# GateDriver.net
KiCad netlist of a schematic drawn in Altium Designer
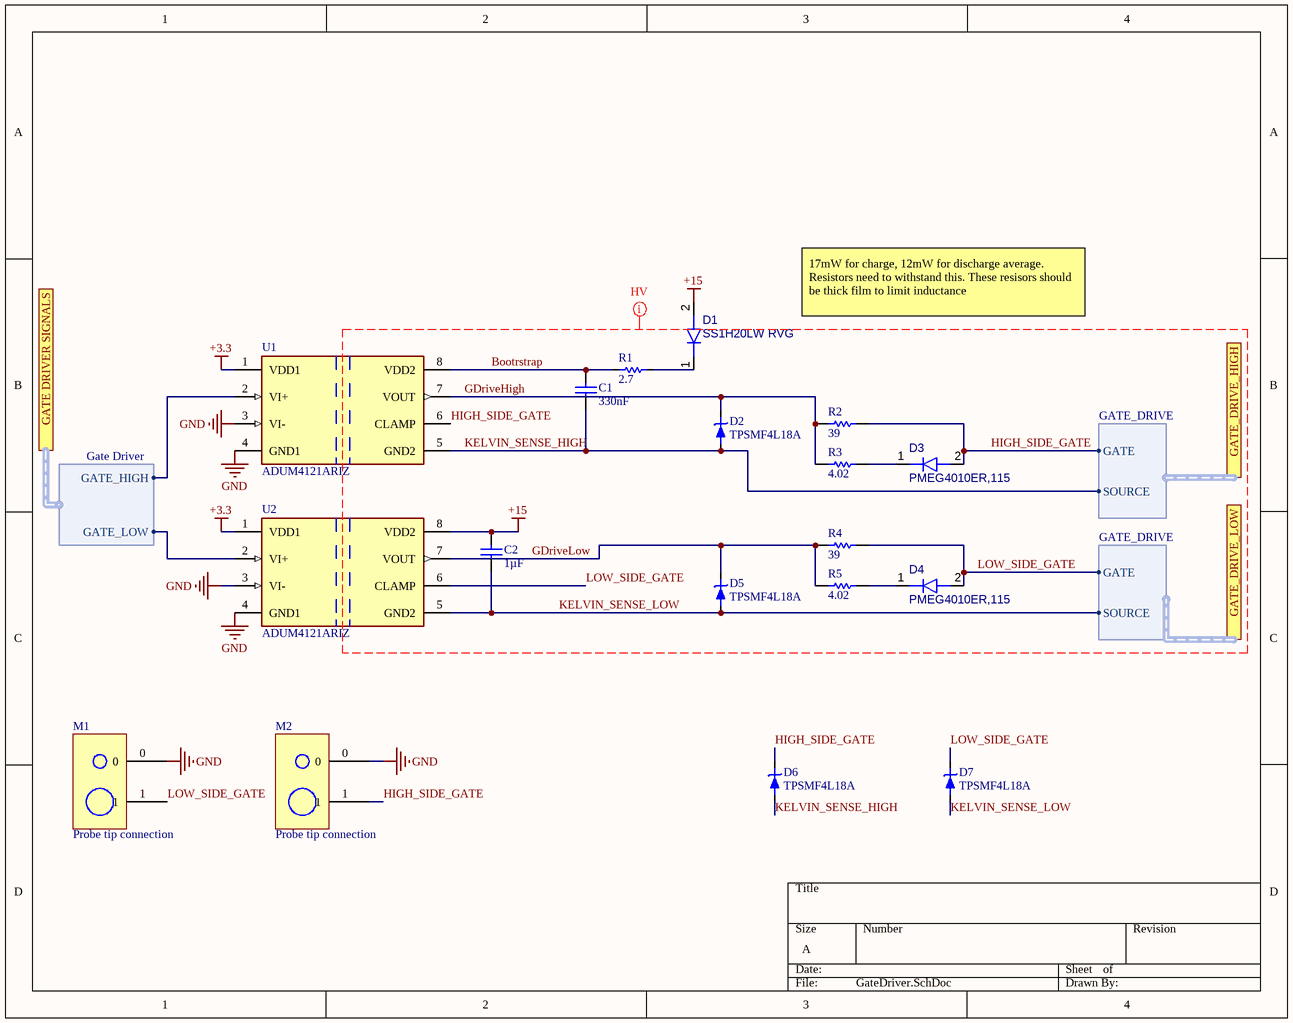
[diagram p0: GateDriver.SchDoc]

(export (version "E")
  (design (tool "Eeschema 10.0.6"))
  (components
    (comp (ref "C1")
      (value "330nF")
      (footprint "1206_CAPACITOR")
      (fields (field (name "TOLERANCE") "10%") (field (name "Comment") "C1206X334K5RACAUTO"))
      (libsource (lib "University of Minnesota - Solar Vehicle Project") (part "Cap"))
    )
    (comp (ref "C2")
      (value "1µF")
      (footprint "0805_Capacitor")
      (description "CAP 0805 1uF 50V")
      (fields (field (name "TOLERANCE") "10%"))
      (libsource (lib "University of Minnesota - Solar Vehicle Project") (part "Cap"))
    )
    (comp (ref "D1")
      (value "SS1H20LW RVG")
      (footprint "PMEG4010ER,115-Footprint-1")
      (description "Rectifier Diode Schottky 200V 1A 2-Pin SOD-123W T/R")
      (libsource (lib "University of Minnesota - Solar Vehicle Project") (part "DIODE-2"))
    )
    (comp (ref "D2")
      (value "TPSMF4L18A")
      (footprint "TPSMF4L18A-Footprint-1")
      (description "TVS DIODE 18V 29.2V SOD123FL")
      (libsource (lib "University of Minnesota - Solar Vehicle Project") (part "D_TV_410V"))
    )
    (comp (ref "D3")
      (value "PMEG4010ER,115")
      (footprint "PMEG4010ER,115-Footprint-1")
      (description "Rectifier Diode, Schottky, 1 Phase, 1 Element, 1A, 40V V(RRM), Silicon")
      (libsource (lib "University of Minnesota - Solar Vehicle Project") (part "DIODE-2"))
    )
    (comp (ref "D4")
      (value "PMEG4010ER,115")
      (footprint "PMEG4010ER,115-Footprint-1")
      (description "Rectifier Diode, Schottky, 1 Phase, 1 Element, 1A, 40V V(RRM), Silicon")
      (libsource (lib "University of Minnesota - Solar Vehicle Project") (part "DIODE-2"))
    )
    (comp (ref "D5")
      (value "TPSMF4L18A")
      (footprint "TPSMF4L18A-Footprint-1")
      (description "TVS DIODE 18V 29.2V SOD123FL")
      (libsource (lib "University of Minnesota - Solar Vehicle Project") (part "D_TV_410V"))
    )
    (comp (ref "D6")
      (value "TPSMF4L18A")
      (footprint "TPSMF4L18A-Footprint-1")
      (description "TVS DIODE 18V 29.2V SOD123FL")
      (libsource (lib "University of Minnesota - Solar Vehicle Project") (part "D_TV_410V"))
    )
    (comp (ref "D7")
      (value "TPSMF4L18A")
      (footprint "TPSMF4L18A-Footprint-1")
      (description "TVS DIODE 18V 29.2V SOD123FL")
      (libsource (lib "University of Minnesota - Solar Vehicle Project") (part "D_TV_410V"))
    )
    (comp (ref "M1")
      (value "Probe tip connection")
      (footprint "Probe tip connection-Footprint-1")
      (description "Connection for oscilscope ground tip")
      (libsource (lib "University of Minnesota - Solar Vehicle Project") (part "Probe tip connection-Symbol-1"))
    )
    (comp (ref "M2")
      (value "Probe tip connection")
      (footprint "Probe tip connection-Footprint-1")
      (description "Connection for oscilscope ground tip")
      (libsource (lib "University of Minnesota - Solar Vehicle Project") (part "Probe tip connection-Symbol-1"))
    )
    (comp (ref "R1")
      (value "2.7")
      (footprint "1210_Resistor")
      (description "RES SMD 2.7 OHM 5% 1/2W 1210")
      (fields (field (name "POWER") "500mW") (field (name "TOLERANCE") "5%"))
      (libsource (lib "University of Minnesota - Solar Vehicle Project") (part "Symbol"))
    )
    (comp (ref "R2")
      (value "39")
      (footprint "0805_Resistor")
      (fields
        (field (name "POWER") "125mW")
        (field (name "TOLERANCE") "5%")
        (field (name "Comment") "RMCF0805JT39R0")
      )
      (libsource (lib "University of Minnesota - Solar Vehicle Project") (part "RES-2"))
    )
    (comp (ref "R3")
      (value "4.02")
      (footprint "0805_Resistor")
      (fields
        (field (name "TOLERANCE") "1%")
        (field (name "POWER") "125mW")
        (field (name "Comment") "CRCW08054R02FKEA")
      )
      (libsource (lib "University of Minnesota - Solar Vehicle Project") (part "RES-2"))
    )
    (comp (ref "R4")
      (value "39")
      (footprint "0805_Resistor")
      (fields
        (field (name "POWER") "125mW")
        (field (name "TOLERANCE") "5%")
        (field (name "Comment") "RMCF0805JT39R0")
      )
      (libsource (lib "University of Minnesota - Solar Vehicle Project") (part "RES-2"))
    )
    (comp (ref "R5")
      (value "4.02")
      (footprint "0805_Resistor")
      (fields
        (field (name "TOLERANCE") "1%")
        (field (name "POWER") "125mW")
        (field (name "Comment") "CRCW08054R02FKEA")
      )
      (libsource (lib "University of Minnesota - Solar Vehicle Project") (part "RES-2"))
    )
    (comp (ref "U1")
      (value "ADUM4121ARIZ")
      (footprint "FP-RI-8-1-IPC_B")
      (description "2A gat driver")
      (libsource (lib "University of Minnesota - Solar Vehicle Project") (part "cd04aab5e6e55e7ffe7a0c5e5a36cba"))
    )
    (comp (ref "U2")
      (value "ADUM4121ARIZ")
      (footprint "FP-RI-8-1-IPC_B")
      (description "2A gat driver")
      (libsource (lib "University of Minnesota - Solar Vehicle Project") (part "cd04aab5e6e55e7ffe7a0c5e5a36cba"))
    )
  )
  (nets
    (net (code "4") (name "+3.3") (class "Default")
      (node (ref "U1") (pin "1") (pinfunction "VDD1_1") (pintype "power_in"))
      (node (ref "U2") (pin "1") (pinfunction "VDD1_1") (pintype "power_in"))
    )
    (net (code "5") (name "+15") (class "Default")
      (node (ref "C2") (pin "2") (pinfunction "2_2") (pintype "passive"))
      (node (ref "D1") (pin "2") (pinfunction "A_2") (pintype "passive"))
      (node (ref "U2") (pin "8") (pinfunction "VDD2_8") (pintype "power_in"))
    )
    (net (code "6") (name "/Bootrstrap") (class "Default")
      (node (ref "C1") (pin "2") (pinfunction "2_2") (pintype "passive"))
      (node (ref "R1") (pin "1") (pinfunction "1_1") (pintype "passive"))
      (node (ref "U1") (pin "8") (pinfunction "VDD2_8") (pintype "power_in"))
    )
    (net (code "7") (name "/GATE_HIGH") (class "Default")
      (node (ref "U1") (pin "2") (pinfunction "VI+_2") (pintype "input"))
    )
    (net (code "8") (name "/GATE_LOW") (class "Default")
      (node (ref "U2") (pin "2") (pinfunction "VI+_2") (pintype "input"))
    )
    (net (code "9") (name "/GDriveHigh") (class "Default")
      (node (ref "D2") (pin "2") (pinfunction "Cathode_2") (pintype "passive"))
      (node (ref "R2") (pin "1") (pinfunction "1_1") (pintype "passive"))
      (node (ref "R3") (pin "1") (pinfunction "1_1") (pintype "passive"))
      (node (ref "U1") (pin "7") (pinfunction "VOUT_7") (pintype "output"))
    )
    (net (code "10") (name "/GDriveLow") (class "Default")
      (node (ref "D5") (pin "2") (pinfunction "Cathode_2") (pintype "passive"))
      (node (ref "R4") (pin "1") (pinfunction "1_1") (pintype "passive"))
      (node (ref "R5") (pin "1") (pinfunction "1_1") (pintype "passive"))
      (node (ref "U2") (pin "7") (pinfunction "VOUT_7") (pintype "output"))
    )
    (net (code "11") (name "/HIGH_SIDE_GATE") (class "Default")
      (node (ref "D3") (pin "2") (pinfunction "A_2") (pintype "passive"))
      (node (ref "D6") (pin "2") (pinfunction "Cathode_2") (pintype "passive"))
      (node (ref "M2") (pin "1") (pinfunction "1_1") (pintype "passive"))
      (node (ref "R2") (pin "2") (pinfunction "2_2") (pintype "passive"))
      (node (ref "U1") (pin "6") (pinfunction "CLAMP_6") (pintype "passive"))
    )
    (net (code "12") (name "/KELVIN_SENSE_HIGH") (class "Default")
      (node (ref "C1") (pin "1") (pinfunction "1_1") (pintype "passive"))
      (node (ref "D2") (pin "1") (pinfunction "Anode_1") (pintype "passive"))
      (node (ref "D6") (pin "1") (pinfunction "Anode_1") (pintype "passive"))
      (node (ref "U1") (pin "5") (pinfunction "GND2_5") (pintype "power_in"))
    )
    (net (code "13") (name "/KELVIN_SENSE_LOW") (class "Default")
      (node (ref "C2") (pin "1") (pinfunction "1_1") (pintype "passive"))
      (node (ref "D5") (pin "1") (pinfunction "Anode_1") (pintype "passive"))
      (node (ref "D7") (pin "1") (pinfunction "Anode_1") (pintype "passive"))
      (node (ref "U2") (pin "5") (pinfunction "GND2_5") (pintype "power_in"))
    )
    (net (code "14") (name "/LOW_SIDE_GATE") (class "Default")
      (node (ref "D4") (pin "2") (pinfunction "A_2") (pintype "passive"))
      (node (ref "D7") (pin "2") (pinfunction "Cathode_2") (pintype "passive"))
      (node (ref "M1") (pin "1") (pinfunction "1_1") (pintype "passive"))
      (node (ref "R4") (pin "2") (pinfunction "2_2") (pintype "passive"))
      (node (ref "U2") (pin "6") (pinfunction "CLAMP_6") (pintype "passive"))
    )
    (net (code "17") (name "GND") (class "Default")
      (node (ref "M1") (pin "0") (pinfunction "0_0") (pintype "passive"))
      (node (ref "M2") (pin "0") (pinfunction "0_0") (pintype "passive"))
      (node (ref "U1") (pin "3") (pinfunction "VI-_3") (pintype "input"))
      (node (ref "U1") (pin "4") (pinfunction "GND1_4") (pintype "power_in"))
      (node (ref "U2") (pin "3") (pinfunction "VI-_3") (pintype "input"))
      (node (ref "U2") (pin "4") (pinfunction "GND1_4") (pintype "power_in"))
    )
    (net (code "18") (name "Net-(D1-K)") (class "Default")
      (node (ref "D1") (pin "1") (pinfunction "K_1") (pintype "passive"))
      (node (ref "R1") (pin "2") (pinfunction "2_2") (pintype "passive"))
    )
    (net (code "19") (name "Net-(D3-K)") (class "Default")
      (node (ref "D3") (pin "1") (pinfunction "K_1") (pintype "passive"))
      (node (ref "R3") (pin "2") (pinfunction "2_2") (pintype "passive"))
    )
    (net (code "20") (name "Net-(D4-K)") (class "Default")
      (node (ref "D4") (pin "1") (pinfunction "K_1") (pintype "passive"))
      (node (ref "R5") (pin "2") (pinfunction "2_2") (pintype "passive"))
    )
  )
)
